# powersupply.net
KiCad netlist of a schematic drawn in EAGLE
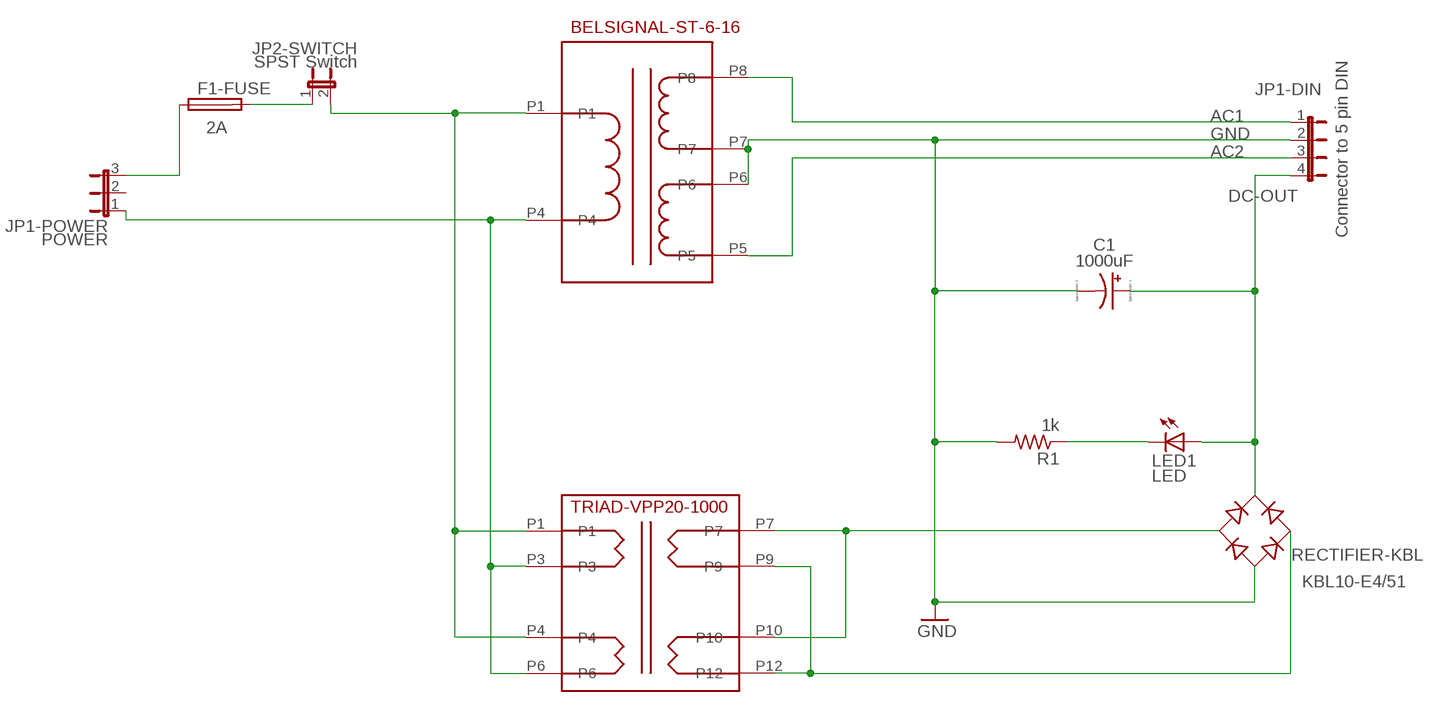
[diagram p0: schematic, sheet 1]

(export (version "E")
  (design (tool "Eeschema 10.0.6"))
  (components
    (comp (ref "BELSIGNAL-ST-6-16")
      (value "ST-6-16")
      (footprint "eagle-import:ST-6-16")
      (libsource (lib "eagle-import") (part "ST-6-16"))
    )
    (comp (ref "C1")
      (value "1000uF")
      (footprint "eagle-import:E3,5-10")
      (libsource (lib "eagle-import") (part "CPOL-USE3.5-10"))
    )
    (comp (ref "F1-FUSE")
      (value "2A")
      (footprint "eagle-import:SH22,5")
      (fields (field (name "MF") "SCHURTER") (field (name "MPN") "0031.8201"))
      (libsource (lib "eagle-import") (part "SH22,5"))
    )
    (comp (ref "JP1-DIN")
      (value "Connector to 5 pin DIN")
      (footprint "eagle-import:JP4")
      (libsource (lib "eagle-import") (part "JP4E"))
    )
    (comp (ref "JP1-POWER")
      (value "POWER")
      (footprint "eagle-import:JP2")
      (libsource (lib "eagle-import") (part "JP2E"))
    )
    (comp (ref "JP2-SWITCH")
      (value "SPST Switch")
      (footprint "eagle-import:JP1")
      (libsource (lib "eagle-import") (part "JP1E"))
    )
    (comp (ref "KBL10-E4/51")
      (value "RECTIFIER-KBL")
      (footprint "eagle-import:KBL")
      (libsource (lib "eagle-import") (part "RECTIFIER-KBL"))
    )
    (comp (ref "LED1")
      (value "LED")
      (footprint "eagle-import:LED5MM")
      (libsource (lib "eagle-import") (part "LED5MM"))
    )
    (comp (ref "R1")
      (value "1k")
      (footprint "eagle-import:0204_7")
      (libsource (lib "eagle-import") (part "R-US_0204/7"))
    )
    (comp (ref "TRIAD-VPP20-1000")
      (value "VPP20-1000")
      (footprint "eagle-import:VPP20-1000")
      (libsource (lib "eagle-import") (part "VPP20-1000"))
    )
  )
  (nets
    (net (code "1") (name "/AC1") (class "Default")
      (node (ref "BELSIGNAL-ST-6-16") (pin "P8") (pinfunction "P8_P8") (pintype "bidirectional"))
      (node (ref "JP1-DIN") (pin "1") (pinfunction "1_1") (pintype "passive"))
    )
    (net (code "2") (name "/AC2") (class "Default")
      (node (ref "BELSIGNAL-ST-6-16") (pin "P5") (pinfunction "P5_P5") (pintype "bidirectional"))
      (node (ref "JP1-DIN") (pin "3") (pinfunction "3_3") (pintype "passive"))
    )
    (net (code "3") (name "/DC-OUT") (class "Default")
      (node (ref "C1") (pin "+") (pinfunction "+_+") (pintype "passive"))
      (node (ref "JP1-DIN") (pin "4") (pinfunction "4_4") (pintype "passive"))
      (node (ref "KBL10-E4/51") (pin "+") (pinfunction "+_+") (pintype "passive"))
      (node (ref "LED1") (pin "A") (pinfunction "A_A") (pintype "passive"))
    )
    (net (code "4") (name "GND") (class "Default")
      (node (ref "BELSIGNAL-ST-6-16") (pin "P6") (pinfunction "P6_P6") (pintype "bidirectional"))
      (node (ref "BELSIGNAL-ST-6-16") (pin "P7") (pinfunction "P7_P7") (pintype "bidirectional"))
      (node (ref "C1") (pin "-") (pinfunction "-_-") (pintype "passive"))
      (node (ref "JP1-DIN") (pin "2") (pinfunction "2_2") (pintype "passive"))
      (node (ref "KBL10-E4/51") (pin "-") (pinfunction "-_-") (pintype "passive"))
      (node (ref "R1") (pin "2") (pinfunction "2_2") (pintype "passive"))
    )
    (net (code "5") (name "Net-(BELSIGNAL-ST-6-16-PadP1)") (class "Default")
      (node (ref "BELSIGNAL-ST-6-16") (pin "P1") (pinfunction "P1_P1") (pintype "bidirectional"))
      (node (ref "JP2-SWITCH") (pin "2") (pinfunction "2_2") (pintype "passive"))
      (node (ref "TRIAD-VPP20-1000") (pin "P1") (pinfunction "P1_P1") (pintype "bidirectional"))
      (node (ref "TRIAD-VPP20-1000") (pin "P4") (pinfunction "P4_P4") (pintype "bidirectional"))
    )
    (net (code "6") (name "Net-(BELSIGNAL-ST-6-16-PadP4)") (class "Default")
      (node (ref "BELSIGNAL-ST-6-16") (pin "P4") (pinfunction "P4_P4") (pintype "bidirectional"))
      (node (ref "JP1-POWER") (pin "1") (pinfunction "1_1") (pintype "passive"))
      (node (ref "TRIAD-VPP20-1000") (pin "P3") (pinfunction "P3_P3") (pintype "bidirectional"))
      (node (ref "TRIAD-VPP20-1000") (pin "P6") (pinfunction "P6_P6") (pintype "bidirectional"))
    )
    (net (code "7") (name "Net-(F1-FUSE-Pad1)") (class "Default")
      (node (ref "F1-FUSE") (pin "1") (pinfunction "1_1") (pintype "passive"))
      (node (ref "JP1-POWER") (pin "3") (pinfunction "3_3") (pintype "passive"))
    )
    (net (code "8") (name "Net-(F1-FUSE-Pad2)") (class "Default")
      (node (ref "F1-FUSE") (pin "2") (pinfunction "2_2") (pintype "passive"))
      (node (ref "JP2-SWITCH") (pin "1") (pinfunction "1_1") (pintype "passive"))
    )
    (net (code "9") (name "Net-(KBL10-E4/51-PadAC1)") (class "Default")
      (node (ref "KBL10-E4/51") (pin "AC1") (pinfunction "AC1_AC1") (pintype "passive"))
      (node (ref "TRIAD-VPP20-1000") (pin "P10") (pinfunction "P10_P10") (pintype "bidirectional"))
      (node (ref "TRIAD-VPP20-1000") (pin "P7") (pinfunction "P7_P7") (pintype "bidirectional"))
    )
    (net (code "10") (name "Net-(KBL10-E4/51-PadAC2)") (class "Default")
      (node (ref "KBL10-E4/51") (pin "AC2") (pinfunction "AC2_AC2") (pintype "passive"))
      (node (ref "TRIAD-VPP20-1000") (pin "P12") (pinfunction "P12_P12") (pintype "bidirectional"))
      (node (ref "TRIAD-VPP20-1000") (pin "P9") (pinfunction "P9_P9") (pintype "bidirectional"))
    )
    (net (code "11") (name "Net-(LED1-C)") (class "Default")
      (node (ref "LED1") (pin "K") (pinfunction "C_K") (pintype "passive"))
      (node (ref "R1") (pin "1") (pinfunction "1_1") (pintype "passive"))
    )
    (net (code "12") (name "unconnected-(JP1-POWER-Pad2)") (class "Default")
      (node (ref "JP1-POWER") (pin "2") (pinfunction "2_2") (pintype "passive"))
    )
  )
)
